# MANEA_TCAD_PROIECT_Sheet2.net
KiCad netlist of a schematic drawn in Altium Designer
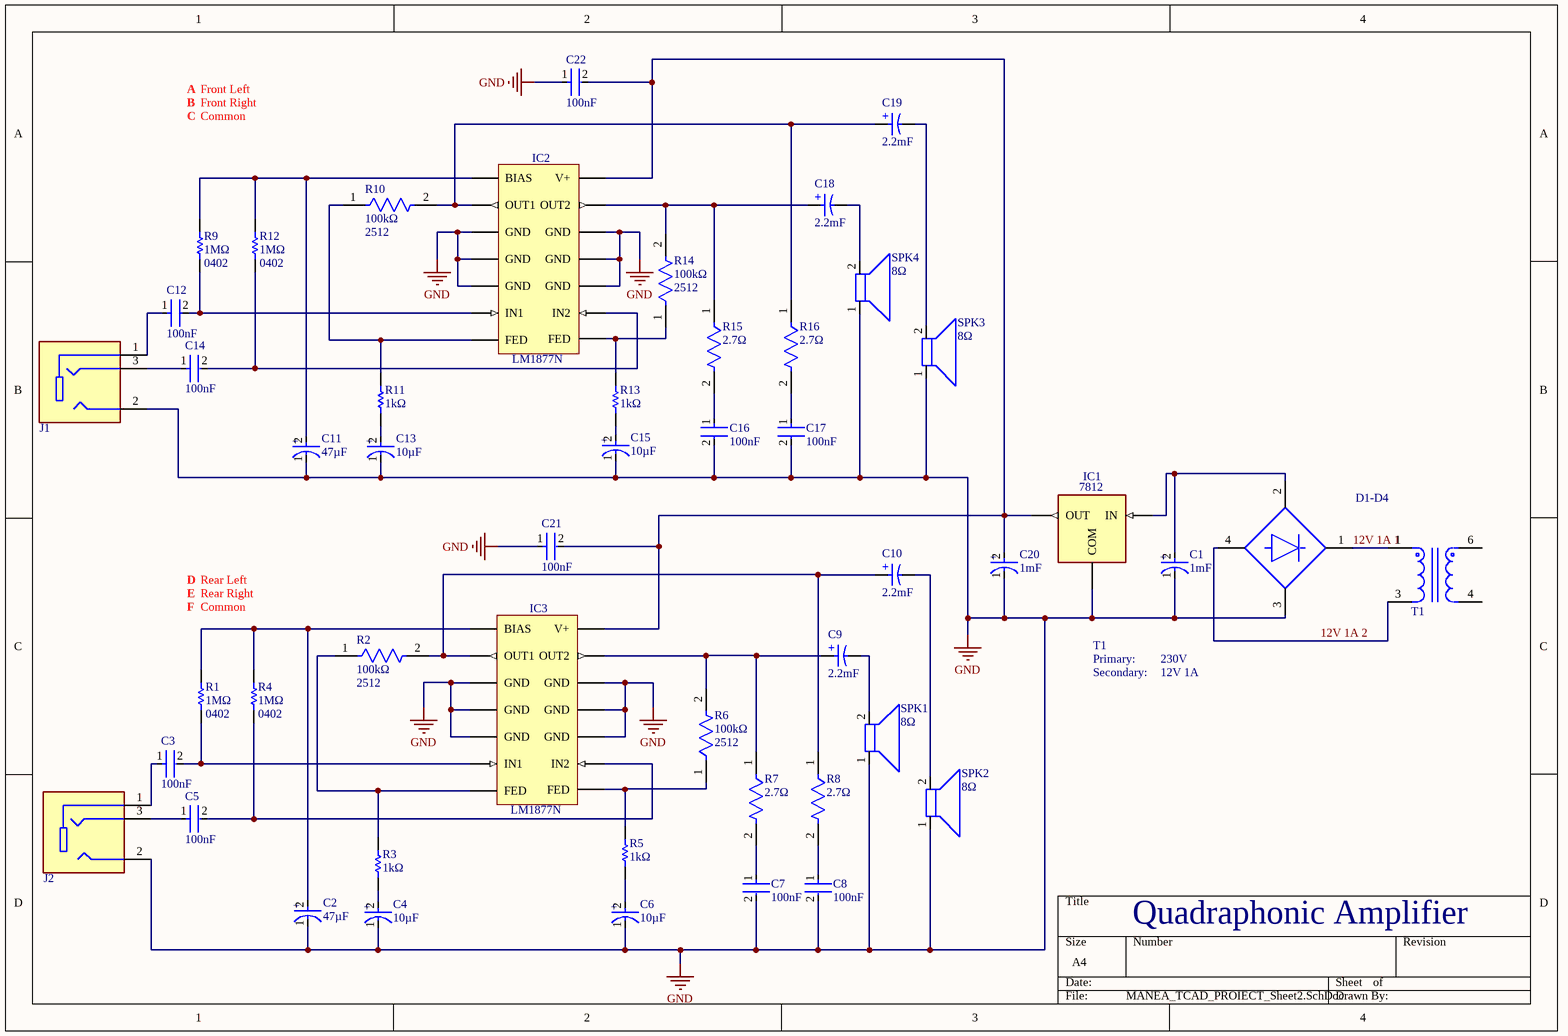
[diagram p0: MANEA_TCAD_PROIECT_Sheet2.SchDoc]

(export (version "E")
  (design (tool "Eeschema 10.0.6"))
  (components
    (comp (ref "C1")
      (value "1mF")
      (footprint "FP-FK-J16-MFG")
      (description "Radial Can - SMD ALUMINUM ELECTROLYTIC CAPACITOR FK 50V 1000muF 卤20% 0.630Dia 16.00mm")
      (fields
        (field (name "MANUFACTURER") "Panasonic")
        (field (name "MANUFACTURER PART NUMBER") "EEV-FK1H102M")
      )
      (libsource (lib "MANEA_TCAD_PROIECT_Schlib") (part "EEV-FK1H102M"))
    )
    (comp (ref "C2")
      (value "47µF")
      (footprint "FP-EDH476M050S9HAA-IPC_A")
      (description "Radial Can - SMD ALUMINUM ELECTROLYTIC CAPACITOR EDH 50V 47muF ±20% 0.248Dia 6.30mm")
      (fields
        (field (name "MANUFACTURER") "Yageo Group")
        (field (name "MANUFACTURER PART NUMBER") "EDH476M050S9HAA")
      )
      (libsource (lib "MANEA_TCAD_PROIECT_Schlib") (part "EDH476M050S9HAA"))
    )
    (comp (ref "C3")
      (value "100nF")
      (footprint "FP-CC0603-DA-MFG")
      (description "Multilayer Ceramic Capacitor, CC Series, 0.1 - F, - 10%, X7R, 50 V, 0603 [1608 Metric]")
      (fields
        (field (name "MANUFACTURER") "Yageo Group")
        (field (name "MANUFACTURER PART NUMBER") "CC0603KRX7R9BB104")
      )
      (libsource (lib "MANEA_TCAD_PROIECT_Schlib") (part "CC0603KRX7R9BB104"))
    )
    (comp (ref "C4")
      (value "10µF")
      (footprint "FP-FPB-MFG")
      (description "Capacitor Aluminum 10uF 16VDC 20% 4 X 5.8mm SMD 0.85 Ohm 160mA 2000 hr Embossed T/R")
      (fields
        (field (name "MANUFACTURER") "Panasonic")
        (field (name "MANUFACTURER PART NUMBER") "EEEFP1C100AR")
      )
      (libsource (lib "MANEA_TCAD_PROIECT_Schlib") (part "EEEFP1C100AR"))
    )
    (comp (ref "C5")
      (value "100nF")
      (footprint "FP-CC0603-DA-MFG")
      (description "Multilayer Ceramic Capacitor, CC Series, 0.1 - F, - 10%, X7R, 50 V, 0603 [1608 Metric]")
      (fields
        (field (name "MANUFACTURER") "Yageo Group")
        (field (name "MANUFACTURER PART NUMBER") "CC0603KRX7R9BB104")
      )
      (libsource (lib "MANEA_TCAD_PROIECT_Schlib") (part "CC0603KRX7R9BB104"))
    )
    (comp (ref "C6")
      (value "10µF")
      (footprint "FP-FPB-MFG")
      (description "Capacitor Aluminum 10uF 16VDC 20% 4 X 5.8mm SMD 0.85 Ohm 160mA 2000 hr Embossed T/R")
      (fields
        (field (name "MANUFACTURER") "Panasonic")
        (field (name "MANUFACTURER PART NUMBER") "EEEFP1C100AR")
      )
      (libsource (lib "MANEA_TCAD_PROIECT_Schlib") (part "EEEFP1C100AR"))
    )
    (comp (ref "C7")
      (value "100nF")
      (footprint "FP-CC0603-DA-MFG")
      (description "Multilayer Ceramic Capacitor, CC Series, 0.1 - F, - 10%, X7R, 50 V, 0603 [1608 Metric]")
      (fields
        (field (name "MANUFACTURER") "Yageo Group")
        (field (name "MANUFACTURER PART NUMBER") "CC0603KRX7R9BB104")
      )
      (libsource (lib "MANEA_TCAD_PROIECT_Schlib") (part "CC0603KRX7R9BB104"))
    )
    (comp (ref "C8")
      (value "100nF")
      (footprint "FP-CC0603-DA-MFG")
      (description "Multilayer Ceramic Capacitor, CC Series, 0.1 - F, - 10%, X7R, 50 V, 0603 [1608 Metric]")
      (fields
        (field (name "MANUFACTURER") "Yageo Group")
        (field (name "MANUFACTURER PART NUMBER") "CC0603KRX7R9BB104")
      )
      (libsource (lib "MANEA_TCAD_PROIECT_Schlib") (part "CC0603KRX7R9BB104"))
    )
    (comp (ref "C9")
      (value "2.2mF")
      (footprint "WCAP-ASLI_D16H17")
      (description "SMD Aluminium Electrolytic Capacitor, WCAP-ASLI Series, 2200 F, 25 V, Radial Can - SMD, 16 mm")
      (fields
        (field (name "MANUFACTURER") "Wurth Elektronik")
        (field (name "MANUFACTURER PART NUMBER") "865080463017")
      )
      (libsource (lib "MANEA_TCAD_PROIECT_Schlib") (part "865080463017"))
    )
    (comp (ref "C10")
      (value "2.2mF")
      (footprint "WCAP-ASLI_D16H17")
      (description "SMD Aluminium Electrolytic Capacitor, WCAP-ASLI Series, 2200 F, 25 V, Radial Can - SMD, 16 mm")
      (fields
        (field (name "MANUFACTURER") "Wurth Elektronik")
        (field (name "MANUFACTURER PART NUMBER") "865080463017")
      )
      (libsource (lib "MANEA_TCAD_PROIECT_Schlib") (part "865080463017"))
    )
    (comp (ref "C11")
      (value "47µF")
      (footprint "FP-EDH476M050S9HAA-IPC_A")
      (description "Radial Can - SMD ALUMINUM ELECTROLYTIC CAPACITOR EDH 50V 47muF ±20% 0.248Dia 6.30mm")
      (fields
        (field (name "MANUFACTURER") "Yageo Group")
        (field (name "MANUFACTURER PART NUMBER") "EDH476M050S9HAA")
      )
      (libsource (lib "MANEA_TCAD_PROIECT_Schlib") (part "EDH476M050S9HAA"))
    )
    (comp (ref "C12")
      (value "100nF")
      (footprint "FP-CC0603-DA-MFG")
      (description "Multilayer Ceramic Capacitor, CC Series, 0.1 - F, - 10%, X7R, 50 V, 0603 [1608 Metric]")
      (fields
        (field (name "MANUFACTURER") "Yageo Group")
        (field (name "MANUFACTURER PART NUMBER") "CC0603KRX7R9BB104")
      )
      (libsource (lib "MANEA_TCAD_PROIECT_Schlib") (part "CC0603KRX7R9BB104"))
    )
    (comp (ref "C13")
      (value "10µF")
      (footprint "FP-FPB-MFG")
      (description "Capacitor Aluminum 10uF 16VDC 20% 4 X 5.8mm SMD 0.85 Ohm 160mA 2000 hr Embossed T/R")
      (fields
        (field (name "MANUFACTURER") "Panasonic")
        (field (name "MANUFACTURER PART NUMBER") "EEEFP1C100AR")
      )
      (libsource (lib "MANEA_TCAD_PROIECT_Schlib") (part "EEEFP1C100AR"))
    )
    (comp (ref "C14")
      (value "100nF")
      (footprint "FP-CC0603-DA-MFG")
      (description "Multilayer Ceramic Capacitor, CC Series, 0.1 - F, - 10%, X7R, 50 V, 0603 [1608 Metric]")
      (fields
        (field (name "MANUFACTURER") "Yageo Group")
        (field (name "MANUFACTURER PART NUMBER") "CC0603KRX7R9BB104")
      )
      (libsource (lib "MANEA_TCAD_PROIECT_Schlib") (part "CC0603KRX7R9BB104"))
    )
    (comp (ref "C15")
      (value "10µF")
      (footprint "FP-FPB-MFG")
      (description "Capacitor Aluminum 10uF 16VDC 20% 4 X 5.8mm SMD 0.85 Ohm 160mA 2000 hr Embossed T/R")
      (fields
        (field (name "MANUFACTURER") "Panasonic")
        (field (name "MANUFACTURER PART NUMBER") "EEEFP1C100AR")
      )
      (libsource (lib "MANEA_TCAD_PROIECT_Schlib") (part "EEEFP1C100AR"))
    )
    (comp (ref "C16")
      (value "100nF")
      (footprint "FP-CC0603-DA-MFG")
      (description "Multilayer Ceramic Capacitor, CC Series, 0.1 - F, - 10%, X7R, 50 V, 0603 [1608 Metric]")
      (fields
        (field (name "MANUFACTURER") "Yageo Group")
        (field (name "MANUFACTURER PART NUMBER") "CC0603KRX7R9BB104")
      )
      (libsource (lib "MANEA_TCAD_PROIECT_Schlib") (part "CC0603KRX7R9BB104"))
    )
    (comp (ref "C17")
      (value "100nF")
      (footprint "FP-CC0603-DA-MFG")
      (description "Multilayer Ceramic Capacitor, CC Series, 0.1 - F, - 10%, X7R, 50 V, 0603 [1608 Metric]")
      (fields
        (field (name "MANUFACTURER") "Yageo Group")
        (field (name "MANUFACTURER PART NUMBER") "CC0603KRX7R9BB104")
      )
      (libsource (lib "MANEA_TCAD_PROIECT_Schlib") (part "CC0603KRX7R9BB104"))
    )
    (comp (ref "C18")
      (value "2.2mF")
      (footprint "WCAP-ASLI_D16H17")
      (description "SMD Aluminium Electrolytic Capacitor, WCAP-ASLI Series, 2200 F, 25 V, Radial Can - SMD, 16 mm")
      (fields
        (field (name "MANUFACTURER") "Wurth Elektronik")
        (field (name "MANUFACTURER PART NUMBER") "865080463017")
      )
      (libsource (lib "MANEA_TCAD_PROIECT_Schlib") (part "865080463017"))
    )
    (comp (ref "C19")
      (value "2.2mF")
      (footprint "WCAP-ASLI_D16H17")
      (description "SMD Aluminium Electrolytic Capacitor, WCAP-ASLI Series, 2200 F, 25 V, Radial Can - SMD, 16 mm")
      (fields
        (field (name "MANUFACTURER") "Wurth Elektronik")
        (field (name "MANUFACTURER PART NUMBER") "865080463017")
      )
      (libsource (lib "MANEA_TCAD_PROIECT_Schlib") (part "865080463017"))
    )
    (comp (ref "C20")
      (value "1mF")
      (footprint "FP-FK-J16-MFG")
      (description "Radial Can - SMD ALUMINUM ELECTROLYTIC CAPACITOR FK 50V 1000muF 卤20% 0.630Dia 16.00mm")
      (fields
        (field (name "MANUFACTURER") "Panasonic")
        (field (name "MANUFACTURER PART NUMBER") "EEV-FK1H102M")
      )
      (libsource (lib "MANEA_TCAD_PROIECT_Schlib") (part "EEV-FK1H102M"))
    )
    (comp (ref "C21")
      (value "100nF")
      (footprint "FP-CC0603-DA-MFG")
      (description "Multilayer Ceramic Capacitor, CC Series, 0.1 - F, - 10%, X7R, 50 V, 0603 [1608 Metric]")
      (fields
        (field (name "MANUFACTURER") "Yageo Group")
        (field (name "MANUFACTURER PART NUMBER") "CC0603KRX7R9BB104")
      )
      (libsource (lib "MANEA_TCAD_PROIECT_Schlib") (part "CC0603KRX7R9BB104"))
    )
    (comp (ref "C22")
      (value "100nF")
      (footprint "FP-CC0603-DA-MFG")
      (description "Multilayer Ceramic Capacitor, CC Series, 0.1 - F, - 10%, X7R, 50 V, 0603 [1608 Metric]")
      (fields
        (field (name "MANUFACTURER") "Yageo Group")
        (field (name "MANUFACTURER PART NUMBER") "CC0603KRX7R9BB104")
      )
      (libsource (lib "MANEA_TCAD_PROIECT_Schlib") (part "CC0603KRX7R9BB104"))
    )
    (comp (ref "D1-D4")
      (value "VS-36MB160A")
      (footprint "FP-95326-MFG")
      (description "Diode, Bridge Rectifier, Vr 1600V, If 35A, Pkg D-34, Vf 1.3V, VS-36MB Series")
      (fields (field (name "MANUFACTURER") "Vishay"))
      (libsource (lib "MANEA_TCAD_PROIECT_Schlib") (part "VS-36MB160A"))
    )
    (comp (ref "IC1")
      (value "LM7812")
      (footprint "TO254P1054X470X1955-3")
      (description "1.5-A, 30-V, linear voltage regulator 3-DDPAK/TO-263 0 to 125")
      (libsource (lib "MANEA_TCAD_PROIECT_Schlib") (part "LM7812"))
    )
    (comp (ref "IC2")
      (value "LM1877N")
      (footprint "DIP254P762X533-14")
      (description "LM1877 Buck Tape & Reel (TR) e3 DC to DC switching controller 400muA 6A 800mum 4.5V")
      (libsource (lib "MANEA_TCAD_PROIECT_Schlib") (part "LM1877N"))
    )
    (comp (ref "IC3")
      (value "LM1877N")
      (footprint "DIP254P762X533-14")
      (description "LM1877 Buck Tape & Reel (TR) e3 DC to DC switching controller 400muA 6A 800mum 4.5V")
      (libsource (lib "MANEA_TCAD_PROIECT_Schlib") (part "LM1877N"))
    )
    (comp (ref "J1")
      (value "SJ1-3523N")
      (footprint "CUI_SJ1-3523N")
      (description "3.5 mm, Stereo, Right Angle, Through Hole, Audio Jack Connector")
      (fields (field (name "MANUFACTURER") "Same Sky"))
      (libsource (lib "MANEA_TCAD_PROIECT_Schlib") (part "SJ1-3523N"))
    )
    (comp (ref "J2")
      (value "SJ1-3523N")
      (footprint "CUI_SJ1-3523N")
      (description "3.5 mm, Stereo, Right Angle, Through Hole, Audio Jack Connector")
      (fields (field (name "MANUFACTURER") "Same Sky"))
      (libsource (lib "MANEA_TCAD_PROIECT_Schlib") (part "SJ1-3523N"))
    )
    (comp (ref "R1")
      (value "1MΩ")
      (footprint "RESC1005X40X25NL05T10")
      (description "Res Thick Film 0402 1M Ohm 1% 0.063W(1/16W) ±100ppm/C Pad SMD T/R")
      (fields
        (field (name "MANUFACTURER") "Yageo Group")
        (field (name "MANUFACTURER PART NUMBER") "RC0402FR-071ML")
        (field (name "CASE/PACKAGE") "0402")
      )
      (libsource (lib "MANEA_TCAD_PROIECT_Schlib") (part "RC0402FR-071ML"))
    )
    (comp (ref "R2")
      (value "100kΩ")
      (footprint "FP-CRGP2512-IPC_A")
      (description "Res Thick Film 2512 100K Ohm 1% 2W ±100ppm/°C Pad SMD T/R Automotive AEC-Q200")
      (fields
        (field (name "MANUFACTURER") "TE Connectivity")
        (field (name "MANUFACTURER PART NUMBER") "CRGP2512F100K")
        (field (name "CASE/PACKAGE") "2512")
      )
      (libsource (lib "MANEA_TCAD_PROIECT_Schlib") (part "CRGP2512F100K"))
    )
    (comp (ref "R3")
      (value "1kΩ")
      (footprint "RESC3116X65X40NL10T20")
      (description "250mW Thick Film Resistors 200V ±100ppm/℃ ±1% 1kΩ 1206 Chip Resistor - Surface Mount ROHS")
      (fields
        (field (name "MANUFACTURER") "Yageo Group")
        (field (name "MANUFACTURER PART NUMBER") "RC1206FR-071KL")
      )
      (libsource (lib "MANEA_TCAD_PROIECT_Schlib") (part "RC1206FR-071KL"))
    )
    (comp (ref "R4")
      (value "1MΩ")
      (footprint "RESC1005X40X25NL05T10")
      (description "Res Thick Film 0402 1M Ohm 1% 0.063W(1/16W) ±100ppm/C Pad SMD T/R")
      (fields
        (field (name "MANUFACTURER") "Yageo Group")
        (field (name "MANUFACTURER PART NUMBER") "RC0402FR-071ML")
        (field (name "CASE/PACKAGE") "0402")
      )
      (libsource (lib "MANEA_TCAD_PROIECT_Schlib") (part "RC0402FR-071ML"))
    )
    (comp (ref "R5")
      (value "1kΩ")
      (footprint "RESC3116X65X40NL10T20")
      (description "250mW Thick Film Resistors 200V ±100ppm/℃ ±1% 1kΩ 1206 Chip Resistor - Surface Mount ROHS")
      (fields
        (field (name "MANUFACTURER") "Yageo Group")
        (field (name "MANUFACTURER PART NUMBER") "RC1206FR-071KL")
      )
      (libsource (lib "MANEA_TCAD_PROIECT_Schlib") (part "RC1206FR-071KL"))
    )
    (comp (ref "R6")
      (value "100kΩ")
      (footprint "FP-CRGP2512-IPC_A")
      (description "Res Thick Film 2512 100K Ohm 1% 2W ±100ppm/°C Pad SMD T/R Automotive AEC-Q200")
      (fields
        (field (name "MANUFACTURER") "TE Connectivity")
        (field (name "MANUFACTURER PART NUMBER") "CRGP2512F100K")
        (field (name "CASE/PACKAGE") "2512")
      )
      (libsource (lib "MANEA_TCAD_PROIECT_Schlib") (part "CRGP2512F100K"))
    )
    (comp (ref "R7")
      (value "2.7Ω")
      (footprint "FP-CR0402-MFG")
      (description "CR0402 FIXED RESISTOR 0402 (1005Metric) Chip Resistor ±5% -250/ +500ppm/C 2.7Ohm 0.063W 1/16W")
      (fields
        (field (name "MANUFACTURER") "Bourns")
        (field (name "MANUFACTURER PART NUMBER") "CR0402-J/-2R7GLF")
      )
      (libsource (lib "MANEA_TCAD_PROIECT_Schlib") (part "CR0402-J/-2R7GLF"))
    )
    (comp (ref "R8")
      (value "2.7Ω")
      (footprint "FP-CR0402-MFG")
      (description "CR0402 FIXED RESISTOR 0402 (1005Metric) Chip Resistor ±5% -250/ +500ppm/C 2.7Ohm 0.063W 1/16W")
      (fields
        (field (name "MANUFACTURER") "Bourns")
        (field (name "MANUFACTURER PART NUMBER") "CR0402-J/-2R7GLF")
      )
      (libsource (lib "MANEA_TCAD_PROIECT_Schlib") (part "CR0402-J/-2R7GLF"))
    )
    (comp (ref "R9")
      (value "1MΩ")
      (footprint "RESC1005X40X25NL05T10")
      (description "Res Thick Film 0402 1M Ohm 1% 0.063W(1/16W) ±100ppm/C Pad SMD T/R")
      (fields
        (field (name "MANUFACTURER") "Yageo Group")
        (field (name "MANUFACTURER PART NUMBER") "RC0402FR-071ML")
        (field (name "CASE/PACKAGE") "0402")
      )
      (libsource (lib "MANEA_TCAD_PROIECT_Schlib") (part "RC0402FR-071ML"))
    )
    (comp (ref "R10")
      (value "100kΩ")
      (footprint "FP-CRGP2512-IPC_A")
      (description "Res Thick Film 2512 100K Ohm 1% 2W ±100ppm/°C Pad SMD T/R Automotive AEC-Q200")
      (fields
        (field (name "MANUFACTURER") "TE Connectivity")
        (field (name "MANUFACTURER PART NUMBER") "CRGP2512F100K")
        (field (name "CASE/PACKAGE") "2512")
      )
      (libsource (lib "MANEA_TCAD_PROIECT_Schlib") (part "CRGP2512F100K"))
    )
    (comp (ref "R11")
      (value "1kΩ")
      (footprint "RESC3116X65X40NL10T20")
      (description "250mW Thick Film Resistors 200V ±100ppm/℃ ±1% 1kΩ 1206 Chip Resistor - Surface Mount ROHS")
      (fields
        (field (name "MANUFACTURER") "Yageo Group")
        (field (name "MANUFACTURER PART NUMBER") "RC1206FR-071KL")
      )
      (libsource (lib "MANEA_TCAD_PROIECT_Schlib") (part "RC1206FR-071KL"))
    )
    (comp (ref "R12")
      (value "1MΩ")
      (footprint "RESC1005X40X25NL05T10")
      (description "Res Thick Film 0402 1M Ohm 1% 0.063W(1/16W) ±100ppm/C Pad SMD T/R")
      (fields
        (field (name "MANUFACTURER") "Yageo Group")
        (field (name "MANUFACTURER PART NUMBER") "RC0402FR-071ML")
        (field (name "CASE/PACKAGE") "0402")
      )
      (libsource (lib "MANEA_TCAD_PROIECT_Schlib") (part "RC0402FR-071ML"))
    )
    (comp (ref "R13")
      (value "1kΩ")
      (footprint "RESC3116X65X40NL10T20")
      (description "250mW Thick Film Resistors 200V ±100ppm/℃ ±1% 1kΩ 1206 Chip Resistor - Surface Mount ROHS")
      (fields
        (field (name "MANUFACTURER") "Yageo Group")
        (field (name "MANUFACTURER PART NUMBER") "RC1206FR-071KL")
      )
      (libsource (lib "MANEA_TCAD_PROIECT_Schlib") (part "RC1206FR-071KL"))
    )
    (comp (ref "R14")
      (value "100kΩ")
      (footprint "FP-CRGP2512-IPC_A")
      (description "Res Thick Film 2512 100K Ohm 1% 2W ±100ppm/°C Pad SMD T/R Automotive AEC-Q200")
      (fields
        (field (name "MANUFACTURER") "TE Connectivity")
        (field (name "MANUFACTURER PART NUMBER") "CRGP2512F100K")
        (field (name "CASE/PACKAGE") "2512")
      )
      (libsource (lib "MANEA_TCAD_PROIECT_Schlib") (part "CRGP2512F100K"))
    )
    (comp (ref "R15")
      (value "2.7Ω")
      (footprint "FP-CR0402-MFG")
      (description "CR0402 FIXED RESISTOR 0402 (1005Metric) Chip Resistor ±5% -250/ +500ppm/C 2.7Ohm 0.063W 1/16W")
      (fields
        (field (name "MANUFACTURER") "Bourns")
        (field (name "MANUFACTURER PART NUMBER") "CR0402-J/-2R7GLF")
      )
      (libsource (lib "MANEA_TCAD_PROIECT_Schlib") (part "CR0402-J/-2R7GLF"))
    )
    (comp (ref "R16")
      (value "2.7Ω")
      (footprint "FP-CR0402-MFG")
      (description "CR0402 FIXED RESISTOR 0402 (1005Metric) Chip Resistor ±5% -250/ +500ppm/C 2.7Ohm 0.063W 1/16W")
      (fields
        (field (name "MANUFACTURER") "Bourns")
        (field (name "MANUFACTURER PART NUMBER") "CR0402-J/-2R7GLF")
      )
      (libsource (lib "MANEA_TCAD_PROIECT_Schlib") (part "CR0402-J/-2R7GLF"))
    )
    (comp (ref "SPK1")
      (value "ASE02808MR-LW150-R")
      (footprint "Manea_Speaker")
      (description "Speakers & Transducers 28mm SPEAKER w/ENCL 2 W 8 OHM 82 DB")
      (fields (field (name "MANUFACTURER") "PUI Audio") (field (name "IMPEDANCE") "8Ω"))
      (libsource (lib "MANEA_TCAD_PROIECT_Schlib") (part "ASE02808MR-LW150-R"))
    )
    (comp (ref "SPK2")
      (value "ASE02808MR-LW150-R")
      (footprint "Manea_Speaker")
      (description "Speakers & Transducers 28mm SPEAKER w/ENCL 2 W 8 OHM 82 DB")
      (fields (field (name "MANUFACTURER") "PUI Audio") (field (name "IMPEDANCE") "8Ω"))
      (libsource (lib "MANEA_TCAD_PROIECT_Schlib") (part "ASE02808MR-LW150-R"))
    )
    (comp (ref "SPK3")
      (value "ASE02808MR-LW150-R")
      (footprint "Manea_Speaker")
      (description "Speakers & Transducers 28mm SPEAKER w/ENCL 2 W 8 OHM 82 DB")
      (fields (field (name "MANUFACTURER") "PUI Audio") (field (name "IMPEDANCE") "8Ω"))
      (libsource (lib "MANEA_TCAD_PROIECT_Schlib") (part "ASE02808MR-LW150-R"))
    )
    (comp (ref "SPK4")
      (value "ASE02808MR-LW150-R")
      (footprint "Manea_Speaker")
      (description "Speakers & Transducers 28mm SPEAKER w/ENCL 2 W 8 OHM 82 DB")
      (fields (field (name "MANUFACTURER") "PUI Audio") (field (name "IMPEDANCE") "8Ω"))
      (libsource (lib "MANEA_TCAD_PROIECT_Schlib") (part "ASE02808MR-LW150-R"))
    )
    (comp (ref "T1")
      (value "PE-68386NL")
      (footprint "FP-PE-68386NL-MFG")
      (description "Pulse Transformer 1: 1 1500VDC 0.6Ohm Prim. DCR 0.6Ohm Sec. DCR 6 Terminal SMD Automotive")
      (fields (field (name "MANUFACTURER") "Yageo Group"))
      (libsource (lib "MANEA_TCAD_PROIECT_Schlib") (part "PE-68386NL"))
    )
  )
  (nets
    (net (code "1") (name "/12V 1A 1") (class "Default")
      (node (ref "D1-D4") (pin "1") (pinfunction "-_1") (pintype "passive"))
      (node (ref "T1") (pin "1") (pinfunction "1_1") (pintype "passive"))
    )
    (net (code "2") (name "/12V 1A 2") (class "Default")
      (node (ref "D1-D4") (pin "4") (pinfunction "+_4") (pintype "passive"))
      (node (ref "T1") (pin "3") (pinfunction "3_3") (pintype "passive"))
    )
    (net (code "3") (name "GND") (class "Default")
      (node (ref "C1") (pin "1") (pinfunction "C_1") (pintype "passive"))
      (node (ref "C11") (pin "1") (pinfunction "C_1") (pintype "passive"))
      (node (ref "C13") (pin "1") (pinfunction "C_1") (pintype "passive"))
      (node (ref "C15") (pin "1") (pinfunction "C_1") (pintype "passive"))
      (node (ref "C16") (pin "2") (pinfunction "2_2") (pintype "passive"))
      (node (ref "C17") (pin "2") (pinfunction "2_2") (pintype "passive"))
      (node (ref "C2") (pin "1") (pinfunction "C_1") (pintype "passive"))
      (node (ref "C20") (pin "1") (pinfunction "C_1") (pintype "passive"))
      (node (ref "C21") (pin "1") (pinfunction "1_1") (pintype "passive"))
      (node (ref "C22") (pin "1") (pinfunction "1_1") (pintype "passive"))
      (node (ref "C4") (pin "1") (pinfunction "C_1") (pintype "passive"))
      (node (ref "C6") (pin "1") (pinfunction "C_1") (pintype "passive"))
      (node (ref "C7") (pin "2") (pinfunction "2_2") (pintype "passive"))
      (node (ref "C8") (pin "2") (pinfunction "2_2") (pintype "passive"))
      (node (ref "D1-D4") (pin "3") (pinfunction "2_~_3") (pintype "passive"))
      (node (ref "IC1") (pin "2") (pinfunction "COM_2") (pintype "passive"))
      (node (ref "IC2") (pin "10") (pinfunction "GND_10") (pintype "passive"))
      (node (ref "IC2") (pin "11") (pinfunction "GND_11") (pintype "passive"))
      (node (ref "IC2") (pin "12") (pinfunction "GND_12") (pintype "passive"))
      (node (ref "IC2") (pin "3") (pinfunction "GND_3") (pintype "passive"))
      (node (ref "IC2") (pin "4") (pinfunction "GND_4") (pintype "power_in"))
      (node (ref "IC2") (pin "5") (pinfunction "GND_5") (pintype "power_in"))
      (node (ref "IC3") (pin "10") (pinfunction "GND_10") (pintype "passive"))
      (node (ref "IC3") (pin "11") (pinfunction "GND_11") (pintype "passive"))
      (node (ref "IC3") (pin "12") (pinfunction "GND_12") (pintype "passive"))
      (node (ref "IC3") (pin "3") (pinfunction "GND_3") (pintype "passive"))
      (node (ref "IC3") (pin "4") (pinfunction "GND_4") (pintype "power_in"))
      (node (ref "IC3") (pin "5") (pinfunction "GND_5") (pintype "power_in"))
      (node (ref "J1") (pin "2") (pinfunction "2_2") (pintype "passive"))
      (node (ref "J2") (pin "2") (pinfunction "2_2") (pintype "passive"))
      (node (ref "SPK1") (pin "1") (pinfunction "1_1") (pintype "passive"))
      (node (ref "SPK2") (pin "1") (pinfunction "1_1") (pintype "passive"))
      (node (ref "SPK3") (pin "1") (pinfunction "1_1") (pintype "passive"))
      (node (ref "SPK4") (pin "1") (pinfunction "1_1") (pintype "passive"))
    )
    (net (code "4") (name "Net-(C1-A)") (class "Default")
      (node (ref "C1") (pin "2") (pinfunction "A_2") (pintype "passive"))
      (node (ref "D1-D4") (pin "2") (pinfunction "1_~_2") (pintype "passive"))
      (node (ref "IC1") (pin "1") (pinfunction "IN_1") (pintype "input"))
    )
    (net (code "5") (name "Net-(C2-A)") (class "Default")
      (node (ref "C2") (pin "2") (pinfunction "A_2") (pintype "passive"))
      (node (ref "IC3") (pin "1") (pinfunction "BIAS_1") (pintype "power_in"))
      (node (ref "R1") (pin "2") (pinfunction "2_2") (pintype "passive"))
      (node (ref "R4") (pin "2") (pinfunction "2_2") (pintype "passive"))
    )
    (net (code "6") (name "Net-(C3-Pad1)") (class "Default")
      (node (ref "C3") (pin "1") (pinfunction "1_1") (pintype "passive"))
      (node (ref "J2") (pin "1") (pinfunction "1_1") (pintype "passive"))
    )
    (net (code "7") (name "Net-(C4-A)") (class "Default")
      (node (ref "C4") (pin "2") (pinfunction "A_2") (pintype "passive"))
      (node (ref "R3") (pin "1") (pinfunction "1_1") (pintype "passive"))
    )
    (net (code "8") (name "Net-(C5-Pad1)") (class "Default")
      (node (ref "C5") (pin "1") (pinfunction "1_1") (pintype "passive"))
      (node (ref "J2") (pin "3") (pinfunction "3_3") (pintype "passive"))
    )
    (net (code "9") (name "Net-(C6-A)") (class "Default")
      (node (ref "C6") (pin "2") (pinfunction "A_2") (pintype "passive"))
      (node (ref "R5") (pin "1") (pinfunction "1_1") (pintype "passive"))
    )
    (net (code "10") (name "Net-(C7-Pad1)") (class "Default")
      (node (ref "C7") (pin "1") (pinfunction "1_1") (pintype "passive"))
      (node (ref "R7") (pin "2") (pinfunction "2_2") (pintype "passive"))
    )
    (net (code "11") (name "Net-(C8-Pad1)") (class "Default")
      (node (ref "C8") (pin "1") (pinfunction "1_1") (pintype "passive"))
      (node (ref "R8") (pin "2") (pinfunction "2_2") (pintype "passive"))
    )
    (net (code "12") (name "Net-(C9-N)") (class "Default")
      (node (ref "C9") (pin "2") (pinfunction "N_2") (pintype "passive"))
      (node (ref "SPK1") (pin "2") (pintype "passive"))
    )
    (net (code "13") (name "Net-(C9-P)") (class "Default")
      (node (ref "C9") (pin "1") (pinfunction "P_1") (pintype "passive"))
      (node (ref "IC3") (pin "13") (pinfunction "OUT2_13") (pintype "output"))
      (node (ref "R6") (pin "2") (pinfunction "2_2") (pintype "passive"))
      (node (ref "R7") (pin "1") (pinfunction "1_1") (pintype "passive"))
    )
    (net (code "14") (name "Net-(C10-N)") (class "Default")
      (node (ref "C10") (pin "2") (pinfunction "N_2") (pintype "passive"))
      (node (ref "SPK2") (pin "2") (pintype "passive"))
    )
    (net (code "15") (name "Net-(C10-P)") (class "Default")
      (node (ref "C10") (pin "1") (pinfunction "P_1") (pintype "passive"))
      (node (ref "IC3") (pin "2") (pinfunction "OUT1_2") (pintype "output"))
      (node (ref "R2") (pin "2") (pinfunction "2_2") (pintype "passive"))
      (node (ref "R8") (pin "1") (pinfunction "1_1") (pintype "passive"))
    )
    (net (code "16") (name "Net-(C11-A)") (class "Default")
      (node (ref "C11") (pin "2") (pinfunction "A_2") (pintype "passive"))
      (node (ref "IC2") (pin "1") (pinfunction "BIAS_1") (pintype "power_in"))
      (node (ref "R12") (pin "2") (pinfunction "2_2") (pintype "passive"))
      (node (ref "R9") (pin "2") (pinfunction "2_2") (pintype "passive"))
    )
    (net (code "17") (name "Net-(C12-Pad1)") (class "Default")
      (node (ref "C12") (pin "1") (pinfunction "1_1") (pintype "passive"))
      (node (ref "J1") (pin "1") (pinfunction "1_1") (pintype "passive"))
    )
    (net (code "18") (name "Net-(C13-A)") (class "Default")
      (node (ref "C13") (pin "2") (pinfunction "A_2") (pintype "passive"))
      (node (ref "R11") (pin "1") (pinfunction "1_1") (pintype "passive"))
    )
    (net (code "19") (name "Net-(C14-Pad1)") (class "Default")
      (node (ref "C14") (pin "1") (pinfunction "1_1") (pintype "passive"))
      (node (ref "J1") (pin "3") (pinfunction "3_3") (pintype "passive"))
    )
    (net (code "20") (name "Net-(C15-A)") (class "Default")
      (node (ref "C15") (pin "2") (pinfunction "A_2") (pintype "passive"))
      (node (ref "R13") (pin "1") (pinfunction "1_1") (pintype "passive"))
    )
    (net (code "21") (name "Net-(C16-Pad1)") (class "Default")
      (node (ref "C16") (pin "1") (pinfunction "1_1") (pintype "passive"))
      (node (ref "R15") (pin "2") (pinfunction "2_2") (pintype "passive"))
    )
    (net (code "22") (name "Net-(C17-Pad1)") (class "Default")
      (node (ref "C17") (pin "1") (pinfunction "1_1") (pintype "passive"))
      (node (ref "R16") (pin "2") (pinfunction "2_2") (pintype "passive"))
    )
    (net (code "23") (name "Net-(C18-N)") (class "Default")
      (node (ref "C18") (pin "2") (pinfunction "N_2") (pintype "passive"))
      (node (ref "SPK4") (pin "2") (pintype "passive"))
    )
    (net (code "24") (name "Net-(C18-P)") (class "Default")
      (node (ref "C18") (pin "1") (pinfunction "P_1") (pintype "passive"))
      (node (ref "IC2") (pin "13") (pinfunction "OUT2_13") (pintype "output"))
      (node (ref "R14") (pin "2") (pinfunction "2_2") (pintype "passive"))
      (node (ref "R15") (pin "1") (pinfunction "1_1") (pintype "passive"))
    )
    (net (code "25") (name "Net-(C19-N)") (class "Default")
      (node (ref "C19") (pin "2") (pinfunction "N_2") (pintype "passive"))
      (node (ref "SPK3") (pin "2") (pintype "passive"))
    )
    (net (code "26") (name "Net-(C19-P)") (class "Default")
      (node (ref "C19") (pin "1") (pinfunction "P_1") (pintype "passive"))
      (node (ref "IC2") (pin "2") (pinfunction "OUT1_2") (pintype "output"))
      (node (ref "R10") (pin "2") (pinfunction "2_2") (pintype "passive"))
      (node (ref "R16") (pin "1") (pinfunction "1_1") (pintype "passive"))
    )
    (net (code "27") (name "Net-(C20-A)") (class "Default")
      (node (ref "C20") (pin "2") (pinfunction "A_2") (pintype "passive"))
      (node (ref "C21") (pin "2") (pinfunction "2_2") (pintype "passive"))
      (node (ref "C22") (pin "2") (pinfunction "2_2") (pintype "passive"))
      (node (ref "IC1") (pin "3") (pinfunction "OUT_3") (pintype "output"))
      (node (ref "IC2") (pin "14") (pinfunction "V+_14") (pintype "passive"))
      (node (ref "IC3") (pin "14") (pinfunction "V+_14") (pintype "passive"))
    )
    (net (code "28") (name "Net-(IC2-FED-Pad7)") (class "Default")
      (node (ref "IC2") (pin "7") (pinfunction "FED_7") (pintype "power_in"))
      (node (ref "R10") (pin "1") (pinfunction "1_1") (pintype "passive"))
      (node (ref "R11") (pin "2") (pinfunction "2_2") (pintype "passive"))
    )
    (net (code "29") (name "Net-(IC2-FED-Pad8)") (class "Default")
      (node (ref "IC2") (pin "8") (pinfunction "FED_8") (pintype "power_in"))
      (node (ref "R13") (pin "2") (pinfunction "2_2") (pintype "passive"))
      (node (ref "R14") (pin "1") (pinfunction "1_1") (pintype "passive"))
    )
    (net (code "30") (name "Net-(IC2-IN1)") (class "Default")
      (node (ref "C12") (pin "2") (pinfunction "2_2") (pintype "passive"))
      (node (ref "IC2") (pin "6") (pinfunction "IN1_6") (pintype "input"))
      (node (ref "R9") (pin "1") (pinfunction "1_1") (pintype "passive"))
    )
    (net (code "31") (name "Net-(IC2-IN2)") (class "Default")
      (node (ref "C14") (pin "2") (pinfunction "2_2") (pintype "passive"))
      (node (ref "IC2") (pin "9") (pinfunction "IN2_9") (pintype "input"))
      (node (ref "R12") (pin "1") (pinfunction "1_1") (pintype "passive"))
    )
    (net (code "32") (name "Net-(IC3-FED-Pad7)") (class "Default")
      (node (ref "IC3") (pin "7") (pinfunction "FED_7") (pintype "power_in"))
      (node (ref "R2") (pin "1") (pinfunction "1_1") (pintype "passive"))
      (node (ref "R3") (pin "2") (pinfunction "2_2") (pintype "passive"))
    )
    (net (code "33") (name "Net-(IC3-FED-Pad8)") (class "Default")
      (node (ref "IC3") (pin "8") (pinfunction "FED_8") (pintype "power_in"))
      (node (ref "R5") (pin "2") (pinfunction "2_2") (pintype "passive"))
      (node (ref "R6") (pin "1") (pinfunction "1_1") (pintype "passive"))
    )
    (net (code "34") (name "Net-(IC3-IN1)") (class "Default")
      (node (ref "C3") (pin "2") (pinfunction "2_2") (pintype "passive"))
      (node (ref "IC3") (pin "6") (pinfunction "IN1_6") (pintype "input"))
      (node (ref "R1") (pin "1") (pinfunction "1_1") (pintype "passive"))
    )
    (net (code "35") (name "Net-(IC3-IN2)") (class "Default")
      (node (ref "C5") (pin "2") (pinfunction "2_2") (pintype "passive"))
      (node (ref "IC3") (pin "9") (pinfunction "IN2_9") (pintype "input"))
      (node (ref "R4") (pin "1") (pinfunction "1_1") (pintype "passive"))
    )
    (net (code "36") (name "unconnected-(T1-Pad4)") (class "Default")
      (node (ref "T1") (pin "4") (pinfunction "4_4") (pintype "passive"))
    )
    (net (code "37") (name "unconnected-(T1-Pad6)") (class "Default")
      (node (ref "T1") (pin "6") (pinfunction "6_6") (pintype "passive"))
    )
  )
)
